# sch.net
KiCad netlist of a schematic drawn in EAGLE
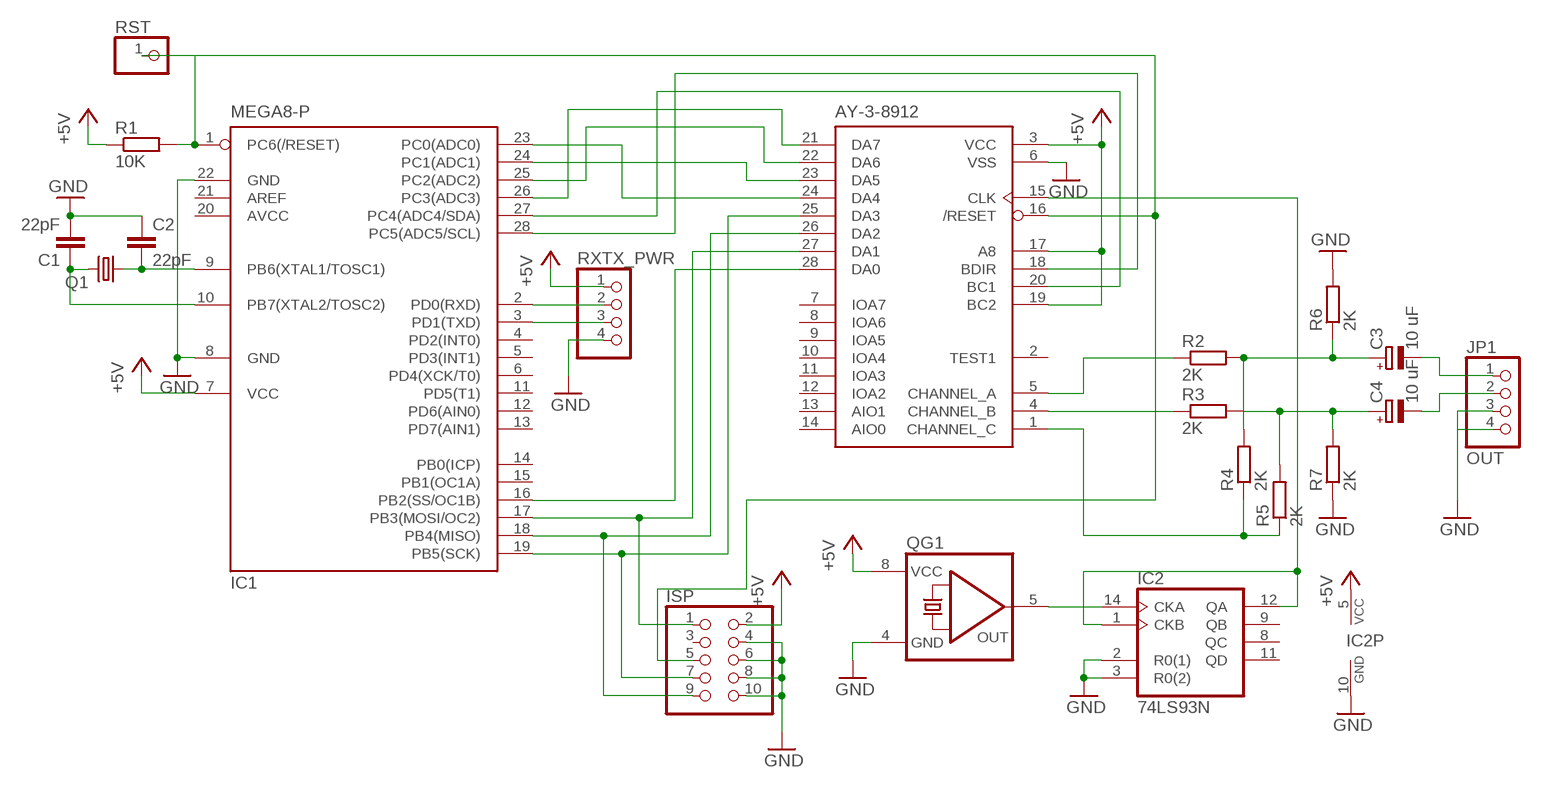
[diagram p0: schematic, sheet 1]

(export (version "E")
  (design (tool "Eeschema 10.0.6"))
  (components
    (comp (ref "AY-3-8912")
      (value "AY-3-8912_28PIN")
      (footprint "eagle-import:DIL28")
      (libsource (lib "eagle-import") (part "AY-3-8912_28PIN"))
    )
    (comp (ref "C1")
      (value "22pF")
      (footprint "eagle-import:C2.5-3")
      (libsource (lib "eagle-import") (part "C2,5-3"))
    )
    (comp (ref "C2")
      (value "22pF")
      (footprint "eagle-import:C2.5-3")
      (libsource (lib "eagle-import") (part "C2,5-3"))
    )
    (comp (ref "C3")
      (value "10 uF")
      (footprint "eagle-import:E2,5-6E")
      (libsource (lib "eagle-import") (part "CPOL-EUE2,5-6E"))
    )
    (comp (ref "C4")
      (value "10 uF")
      (footprint "eagle-import:E2,5-6E")
      (libsource (lib "eagle-import") (part "CPOL-EUE2,5-6E"))
    )
    (comp (ref "IC1")
      (value "MEGA8-P")
      (footprint "eagle-import:DIL28-3")
      (libsource (lib "eagle-import") (part "MEGA8-P"))
    )
    (comp (ref "IC2")
      (value "74LS93N")
      (footprint "eagle-import:DIL14")
      (libsource (lib "eagle-import") (part "7493NLS"))
    )
    (comp (ref "ISP")
      (value "PINHD-2X5")
      (footprint "eagle-import:2X05")
      (libsource (lib "eagle-import") (part "PINHD-2X5"))
    )
    (comp (ref "JP1")
      (value "OUT")
      (footprint "eagle-import:1X04")
      (libsource (lib "eagle-import") (part "PINHD-1X4"))
    )
    (comp (ref "Q1")
      (value "CRYSTALHC49U-V")
      (footprint "eagle-import:HC49U-V")
      (libsource (lib "eagle-import") (part "CRYSTALHC49U-V"))
    )
    (comp (ref "QG1")
      (value "QG5460")
      (footprint "eagle-import:DIL08S")
      (libsource (lib "eagle-import") (part "QG5460"))
    )
    (comp (ref "R1")
      (value "10K")
      (footprint "eagle-import:0204_7")
      (libsource (lib "eagle-import") (part "R-EU_0204/7"))
    )
    (comp (ref "R2")
      (value "2K")
      (footprint "eagle-import:0204_7")
      (libsource (lib "eagle-import") (part "R-EU_0204/7"))
    )
    (comp (ref "R3")
      (value "2K")
      (footprint "eagle-import:0204_7")
      (libsource (lib "eagle-import") (part "R-EU_0204/7"))
    )
    (comp (ref "R4")
      (value "2K")
      (footprint "eagle-import:0204_7")
      (libsource (lib "eagle-import") (part "R-EU_0204/7"))
    )
    (comp (ref "R5")
      (value "2K")
      (footprint "eagle-import:0204_7")
      (libsource (lib "eagle-import") (part "R-EU_0204/7"))
    )
    (comp (ref "R6")
      (value "2K")
      (footprint "eagle-import:0204_7")
      (libsource (lib "eagle-import") (part "R-EU_0204/7"))
    )
    (comp (ref "R7")
      (value "2K")
      (footprint "eagle-import:0204_7")
      (libsource (lib "eagle-import") (part "R-EU_0204/7"))
    )
    (comp (ref "RST")
      (value "PINHD-1X1")
      (footprint "eagle-import:1X01")
      (libsource (lib "eagle-import") (part "PINHD-1X1"))
    )
    (comp (ref "RXTX_PWR")
      (value "PINHD-1X4")
      (footprint "eagle-import:1X04")
      (libsource (lib "eagle-import") (part "PINHD-1X4"))
    )
  )
  (nets
    (net (code "1") (name "+5V") (class "Default")
      (node (ref "AY-3-8912") (pin "17") (pinfunction "A8_17") (pintype "input"))
      (node (ref "AY-3-8912") (pin "19") (pinfunction "BC2_19") (pintype "input"))
      (node (ref "AY-3-8912") (pin "3") (pinfunction "VCC_3") (pintype "power_in"))
      (node (ref "IC1") (pin "7") (pinfunction "VCC_7") (pintype "power_in"))
      (node (ref "IC2") (pin "5") (pinfunction "VCC_5") (pintype "power_in"))
      (node (ref "ISP") (pin "2") (pinfunction "2_2") (pintype "passive"))
      (node (ref "QG1") (pin "8") (pinfunction "VCC_8") (pintype "power_in"))
      (node (ref "R1") (pin "1") (pinfunction "1_1") (pintype "passive"))
      (node (ref "RXTX_PWR") (pin "1") (pinfunction "1_1") (pintype "passive"))
    )
    (net (code "2") (name "/AVCC") (class "Default")
      (node (ref "IC1") (pin "20") (pinfunction "AVCC_20") (pintype "power_in"))
    )
    (net (code "3") (name "GND") (class "Default")
      (node (ref "AY-3-8912") (pin "6") (pinfunction "VSS_6") (pintype "power_in"))
      (node (ref "C1") (pin "2") (pinfunction "2_2") (pintype "passive"))
      (node (ref "C2") (pin "1") (pinfunction "1_1") (pintype "passive"))
      (node (ref "IC1") (pin "22") (pinfunction "GND_22") (pintype "power_in"))
      (node (ref "IC1") (pin "8") (pinfunction "GND_8") (pintype "power_in"))
      (node (ref "IC2") (pin "10") (pinfunction "GND_10") (pintype "power_in"))
      (node (ref "IC2") (pin "2") (pinfunction "R0(1)_2") (pintype "input"))
      (node (ref "IC2") (pin "3") (pinfunction "R0(2)_3") (pintype "input"))
      (node (ref "ISP") (pin "10") (pinfunction "10_10") (pintype "passive"))
      (node (ref "ISP") (pin "4") (pinfunction "4_4") (pintype "passive"))
      (node (ref "ISP") (pin "6") (pinfunction "6_6") (pintype "passive"))
      (node (ref "ISP") (pin "8") (pinfunction "8_8") (pintype "passive"))
      (node (ref "JP1") (pin "3") (pinfunction "3_3") (pintype "passive"))
      (node (ref "JP1") (pin "4") (pinfunction "4_4") (pintype "passive"))
      (node (ref "QG1") (pin "4") (pinfunction "GND_4") (pintype "power_in"))
      (node (ref "R6") (pin "2") (pinfunction "2_2") (pintype "passive"))
      (node (ref "R7") (pin "1") (pinfunction "1_1") (pintype "passive"))
      (node (ref "RXTX_PWR") (pin "4") (pinfunction "4_4") (pintype "passive"))
    )
    (net (code "4") (name "Net-(AY-3-8912-BC1)") (class "Default")
      (node (ref "AY-3-8912") (pin "20") (pinfunction "BC1_20") (pintype "input"))
      (node (ref "IC1") (pin "27") (pinfunction "PC4(ADC4/SDA)_27") (pintype "bidirectional"))
    )
    (net (code "5") (name "Net-(AY-3-8912-BDIR)") (class "Default")
      (node (ref "AY-3-8912") (pin "18") (pinfunction "BDIR_18") (pintype "input"))
      (node (ref "IC1") (pin "28") (pinfunction "PC5(ADC5/SCL)_28") (pintype "bidirectional"))
    )
    (net (code "6") (name "Net-(AY-3-8912-CHANNEL_A)") (class "Default")
      (node (ref "AY-3-8912") (pin "5") (pinfunction "CHANNEL_A_5") (pintype "output"))
      (node (ref "R2") (pin "1") (pinfunction "1_1") (pintype "passive"))
    )
    (net (code "7") (name "Net-(AY-3-8912-CHANNEL_B)") (class "Default")
      (node (ref "AY-3-8912") (pin "4") (pinfunction "CHANNEL_B_4") (pintype "output"))
      (node (ref "R3") (pin "1") (pinfunction "1_1") (pintype "passive"))
    )
    (net (code "8") (name "Net-(AY-3-8912-CHANNEL_C)") (class "Default")
      (node (ref "AY-3-8912") (pin "1") (pinfunction "CHANNEL_C_1") (pintype "output"))
      (node (ref "R4") (pin "1") (pinfunction "1_1") (pintype "passive"))
      (node (ref "R5") (pin "1") (pinfunction "1_1") (pintype "passive"))
    )
    (net (code "9") (name "Net-(AY-3-8912-CLK)") (class "Default")
      (node (ref "AY-3-8912") (pin "15") (pinfunction "CLK_15") (pintype "input"))
      (node (ref "IC2") (pin "1") (pinfunction "CKB_1") (pintype "input"))
      (node (ref "IC2") (pin "12") (pinfunction "QA_12") (pintype "output"))
    )
    (net (code "10") (name "Net-(AY-3-8912-DA0)") (class "Default")
      (node (ref "AY-3-8912") (pin "28") (pinfunction "DA0_28") (pintype "bidirectional"))
      (node (ref "IC1") (pin "16") (pinfunction "PB2(SS/OC1B)_16") (pintype "bidirectional"))
    )
    (net (code "11") (name "Net-(AY-3-8912-DA1)") (class "Default")
      (node (ref "AY-3-8912") (pin "27") (pinfunction "DA1_27") (pintype "bidirectional"))
      (node (ref "IC1") (pin "17") (pinfunction "PB3(MOSI/OC2)_17") (pintype "bidirectional"))
      (node (ref "ISP") (pin "1") (pinfunction "1_1") (pintype "passive"))
    )
    (net (code "12") (name "Net-(AY-3-8912-DA2)") (class "Default")
      (node (ref "AY-3-8912") (pin "26") (pinfunction "DA2_26") (pintype "bidirectional"))
      (node (ref "IC1") (pin "18") (pinfunction "PB4(MISO)_18") (pintype "bidirectional"))
      (node (ref "ISP") (pin "9") (pinfunction "9_9") (pintype "passive"))
    )
    (net (code "13") (name "Net-(AY-3-8912-DA3)") (class "Default")
      (node (ref "AY-3-8912") (pin "25") (pinfunction "DA3_25") (pintype "bidirectional"))
      (node (ref "IC1") (pin "19") (pinfunction "PB5(SCK)_19") (pintype "bidirectional"))
      (node (ref "ISP") (pin "7") (pinfunction "7_7") (pintype "passive"))
    )
    (net (code "14") (name "Net-(AY-3-8912-DA4)") (class "Default")
      (node (ref "AY-3-8912") (pin "24") (pinfunction "DA4_24") (pintype "bidirectional"))
      (node (ref "IC1") (pin "23") (pinfunction "PC0(ADC0)_23") (pintype "bidirectional"))
    )
    (net (code "15") (name "Net-(AY-3-8912-DA5)") (class "Default")
      (node (ref "AY-3-8912") (pin "23") (pinfunction "DA5_23") (pintype "bidirectional"))
      (node (ref "IC1") (pin "24") (pinfunction "PC1(ADC1)_24") (pintype "bidirectional"))
    )
    (net (code "16") (name "Net-(AY-3-8912-DA6)") (class "Default")
      (node (ref "AY-3-8912") (pin "22") (pinfunction "DA6_22") (pintype "bidirectional"))
      (node (ref "IC1") (pin "25") (pinfunction "PC2(ADC2)_25") (pintype "bidirectional"))
    )
    (net (code "17") (name "Net-(AY-3-8912-DA7)") (class "Default")
      (node (ref "AY-3-8912") (pin "21") (pinfunction "DA7_21") (pintype "bidirectional"))
      (node (ref "IC1") (pin "26") (pinfunction "PC3(ADC3)_26") (pintype "bidirectional"))
    )
    (net (code "18") (name "Net-(AY-3-8912-{slash}RESET)") (class "Default")
      (node (ref "AY-3-8912") (pin "16") (pinfunction "/RESET_16") (pintype "input"))
      (node (ref "IC1") (pin "1") (pinfunction "PC6(/RESET)_1") (pintype "bidirectional"))
      (node (ref "ISP") (pin "5") (pinfunction "5_5") (pintype "passive"))
      (node (ref "R1") (pin "2") (pinfunction "2_2") (pintype "passive"))
      (node (ref "RST") (pin "1") (pinfunction "1_1") (pintype "passive"))
    )
    (net (code "19") (name "Net-(C3-Pad+)") (class "Default")
      (node (ref "C3") (pin "+") (pinfunction "+_+") (pintype "passive"))
      (node (ref "R2") (pin "2") (pinfunction "2_2") (pintype "passive"))
      (node (ref "R4") (pin "2") (pinfunction "2_2") (pintype "passive"))
      (node (ref "R6") (pin "1") (pinfunction "1_1") (pintype "passive"))
    )
    (net (code "20") (name "Net-(C3-Pad-)") (class "Default")
      (node (ref "C3") (pin "-") (pinfunction "-_-") (pintype "passive"))
      (node (ref "JP1") (pin "1") (pinfunction "1_1") (pintype "passive"))
    )
    (net (code "21") (name "Net-(C4-Pad+)") (class "Default")
      (node (ref "C4") (pin "+") (pinfunction "+_+") (pintype "passive"))
      (node (ref "R3") (pin "2") (pinfunction "2_2") (pintype "passive"))
      (node (ref "R5") (pin "2") (pinfunction "2_2") (pintype "passive"))
      (node (ref "R7") (pin "2") (pinfunction "2_2") (pintype "passive"))
    )
    (net (code "22") (name "Net-(C4-Pad-)") (class "Default")
      (node (ref "C4") (pin "-") (pinfunction "-_-") (pintype "passive"))
      (node (ref "JP1") (pin "2") (pinfunction "2_2") (pintype "passive"))
    )
    (net (code "23") (name "Net-(IC1-PB6(XTAL1{slash}TOSC1))") (class "Default")
      (node (ref "C2") (pin "2") (pinfunction "2_2") (pintype "passive"))
      (node (ref "IC1") (pin "9") (pinfunction "PB6(XTAL1/TOSC1)_9") (pintype "bidirectional"))
      (node (ref "Q1") (pin "1") (pinfunction "1_1") (pintype "passive"))
    )
    (net (code "24") (name "Net-(IC1-PB7(XTAL2{slash}TOSC2))") (class "Default")
      (node (ref "C1") (pin "1") (pinfunction "1_1") (pintype "passive"))
      (node (ref "IC1") (pin "10") (pinfunction "PB7(XTAL2/TOSC2)_10") (pintype "bidirectional"))
      (node (ref "Q1") (pin "2") (pinfunction "2_2") (pintype "passive"))
    )
    (net (code "25") (name "Net-(IC1-PD0(RXD))") (class "Default")
      (node (ref "IC1") (pin "2") (pinfunction "PD0(RXD)_2") (pintype "bidirectional"))
      (node (ref "RXTX_PWR") (pin "2") (pinfunction "2_2") (pintype "passive"))
    )
    (net (code "26") (name "Net-(IC1-PD1(TXD))") (class "Default")
      (node (ref "IC1") (pin "3") (pinfunction "PD1(TXD)_3") (pintype "bidirectional"))
      (node (ref "RXTX_PWR") (pin "3") (pinfunction "3_3") (pintype "passive"))
    )
    (net (code "27") (name "Net-(IC2A-CKA)") (class "Default")
      (node (ref "IC2") (pin "14") (pinfunction "CKA_14") (pintype "input"))
      (node (ref "QG1") (pin "5") (pinfunction "OUT_5") (pintype "output"))
    )
    (net (code "28") (name "unconnected-(AY-3-8912-AIO0-Pad14)") (class "Default")
      (node (ref "AY-3-8912") (pin "14") (pinfunction "AIO0_14") (pintype "bidirectional"))
    )
    (net (code "29") (name "unconnected-(AY-3-8912-AIO1-Pad13)") (class "Default")
      (node (ref "AY-3-8912") (pin "13") (pinfunction "AIO1_13") (pintype "bidirectional"))
    )
    (net (code "30") (name "unconnected-(AY-3-8912-IOA2-Pad12)") (class "Default")
      (node (ref "AY-3-8912") (pin "12") (pinfunction "IOA2_12") (pintype "bidirectional"))
    )
    (net (code "31") (name "unconnected-(AY-3-8912-IOA3-Pad11)") (class "Default")
      (node (ref "AY-3-8912") (pin "11") (pinfunction "IOA3_11") (pintype "bidirectional"))
    )
    (net (code "32") (name "unconnected-(AY-3-8912-IOA4-Pad10)") (class "Default")
      (node (ref "AY-3-8912") (pin "10") (pinfunction "IOA4_10") (pintype "bidirectional"))
    )
    (net (code "33") (name "unconnected-(AY-3-8912-IOA5-Pad9)") (class "Default")
      (node (ref "AY-3-8912") (pin "9") (pinfunction "IOA5_9") (pintype "bidirectional"))
    )
    (net (code "34") (name "unconnected-(AY-3-8912-IOA6-Pad8)") (class "Default")
      (node (ref "AY-3-8912") (pin "8") (pinfunction "IOA6_8") (pintype "bidirectional"))
    )
    (net (code "35") (name "unconnected-(AY-3-8912-IOA7-Pad7)") (class "Default")
      (node (ref "AY-3-8912") (pin "7") (pinfunction "IOA7_7") (pintype "bidirectional"))
    )
    (net (code "36") (name "unconnected-(AY-3-8912-TEST1-Pad2)") (class "Default")
      (node (ref "AY-3-8912") (pin "2") (pinfunction "TEST1_2") (pintype "no_connect"))
    )
    (net (code "37") (name "unconnected-(IC1-AREF-Pad21)") (class "Default")
      (node (ref "IC1") (pin "21") (pinfunction "AREF_21") (pintype "passive"))
    )
    (net (code "38") (name "unconnected-(IC1-PB0(ICP)-Pad14)") (class "Default")
      (node (ref "IC1") (pin "14") (pinfunction "PB0(ICP)_14") (pintype "bidirectional"))
    )
    (net (code "39") (name "unconnected-(IC1-PB1(OC1A)-Pad15)") (class "Default")
      (node (ref "IC1") (pin "15") (pinfunction "PB1(OC1A)_15") (pintype "bidirectional"))
    )
    (net (code "40") (name "unconnected-(IC1-PD2(INT0)-Pad4)") (class "Default")
      (node (ref "IC1") (pin "4") (pinfunction "PD2(INT0)_4") (pintype "bidirectional"))
    )
    (net (code "41") (name "unconnected-(IC1-PD3(INT1)-Pad5)") (class "Default")
      (node (ref "IC1") (pin "5") (pinfunction "PD3(INT1)_5") (pintype "bidirectional"))
    )
    (net (code "42") (name "unconnected-(IC1-PD4(XCK{slash}T0)-Pad6)") (class "Default")
      (node (ref "IC1") (pin "6") (pinfunction "PD4(XCK/T0)_6") (pintype "bidirectional"))
    )
    (net (code "43") (name "unconnected-(IC1-PD5(T1)-Pad11)") (class "Default")
      (node (ref "IC1") (pin "11") (pinfunction "PD5(T1)_11") (pintype "bidirectional"))
    )
    (net (code "44") (name "unconnected-(IC1-PD6(AIN0)-Pad12)") (class "Default")
      (node (ref "IC1") (pin "12") (pinfunction "PD6(AIN0)_12") (pintype "bidirectional"))
    )
    (net (code "45") (name "unconnected-(IC1-PD7(AIN1)-Pad13)") (class "Default")
      (node (ref "IC1") (pin "13") (pinfunction "PD7(AIN1)_13") (pintype "bidirectional"))
    )
    (net (code "46") (name "unconnected-(IC2A-QB-Pad9)") (class "Default")
      (node (ref "IC2") (pin "9") (pinfunction "QB_9") (pintype "output"))
    )
    (net (code "47") (name "unconnected-(IC2A-QC-Pad8)") (class "Default")
      (node (ref "IC2") (pin "8") (pinfunction "QC_8") (pintype "output"))
    )
    (net (code "48") (name "unconnected-(IC2A-QD-Pad11)") (class "Default")
      (node (ref "IC2") (pin "11") (pinfunction "QD_11") (pintype "output"))
    )
    (net (code "49") (name "unconnected-(ISP-Pad3)") (class "Default")
      (node (ref "ISP") (pin "3") (pinfunction "3_3") (pintype "passive"))
    )
  )
)
